# User_Interface.net
KiCad netlist of a schematic drawn in Altium Designer
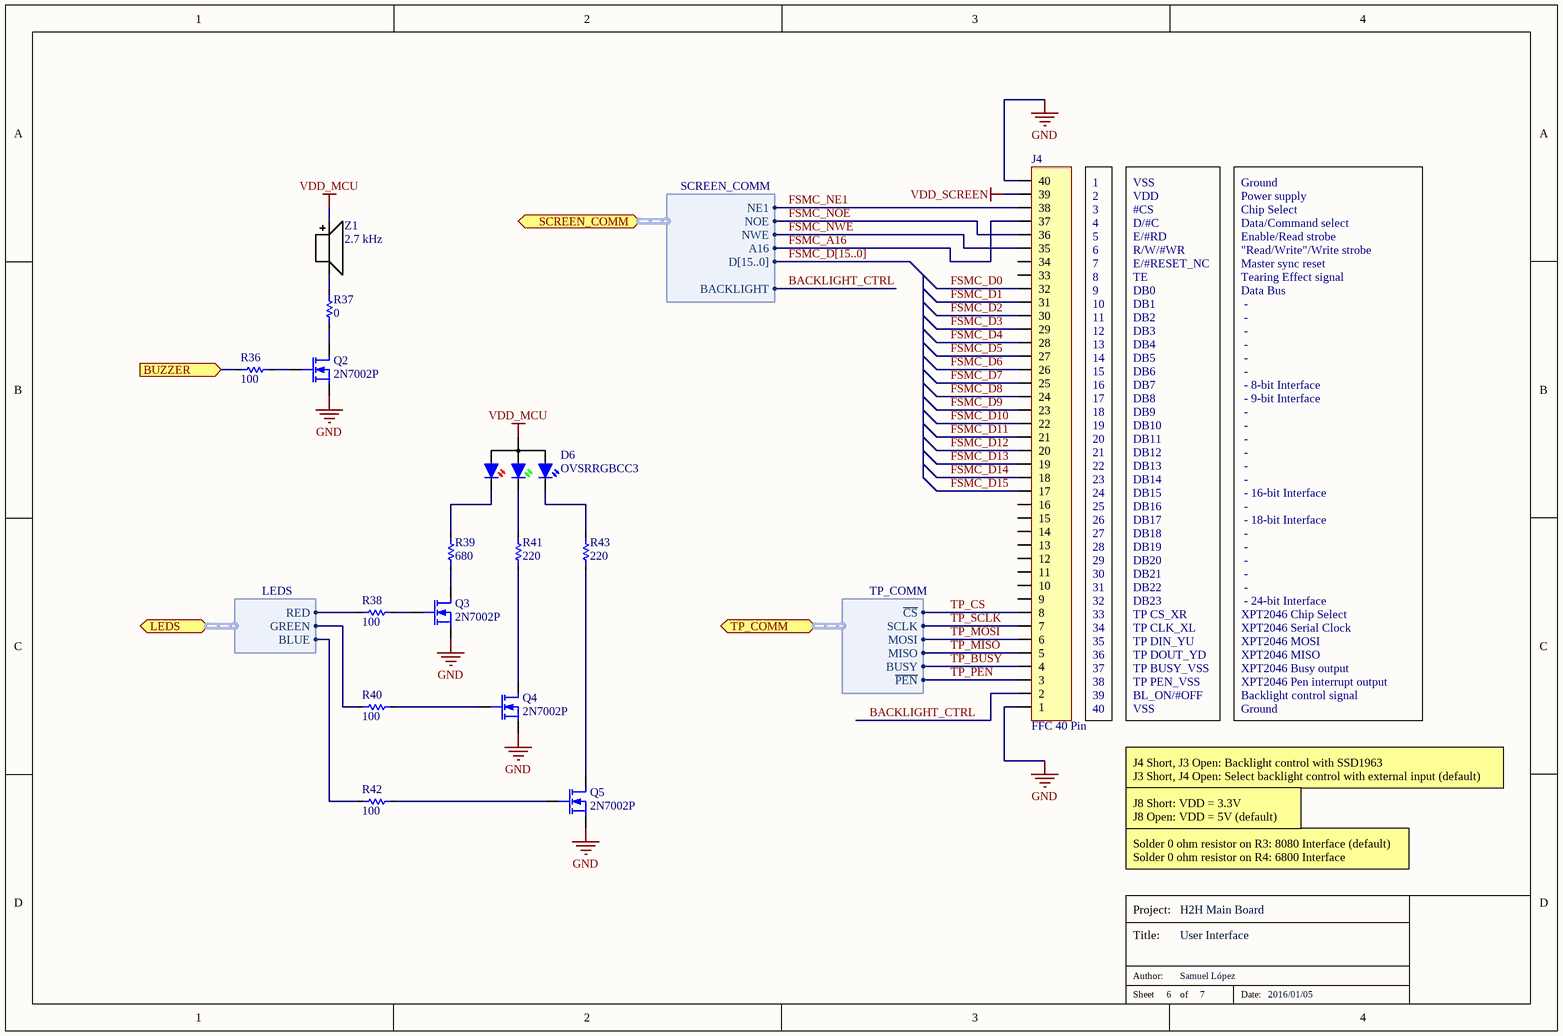
[diagram p0: User Interface.SchDoc]

(export (version "E")
  (design (tool "Eeschema 10.0.6"))
  (components
    (comp (ref "D6")
      (value "OVSRRGBCC3")
      (footprint "OVSRRGBCC3/SIDE")
      (description "LED - RGB, Top/Side-emmiting")
      (libsource (lib "H2H") (part "OVSRRGBCC3"))
    )
    (comp (ref "J4")
      (value "FFC 40 Pin")
      (footprint "ER-CON40HB-2")
      (description "Conn - FFC/FPC, 40 Pin, 1.0mm Pitch, ZIF")
      (libsource (lib "Conn") (part "ER-CON40HB-2"))
    )
    (comp (ref "Q2")
      (value "2N7002P")
      (footprint "2N7002P")
      (description "Transistor - MOSFET, N-Channel, 60V, 300mA")
      (libsource (lib "H2H") (part "2N7002P"))
    )
    (comp (ref "Q3")
      (value "2N7002P")
      (footprint "2N7002P")
      (description "Transistor - MOSFET, N-Channel, 60V, 300mA")
      (libsource (lib "H2H") (part "2N7002P"))
    )
    (comp (ref "Q4")
      (value "2N7002P")
      (footprint "2N7002P")
      (description "Transistor - MOSFET, N-Channel, 60V, 300mA")
      (libsource (lib "H2H") (part "2N7002P"))
    )
    (comp (ref "Q5")
      (value "2N7002P")
      (footprint "2N7002P")
      (description "Transistor - MOSFET, N-Channel, 60V, 300mA")
      (libsource (lib "H2H") (part "2N7002P"))
    )
    (comp (ref "R36")
      (value "100")
      (footprint "R0603")
      (description "Resistor")
      (libsource (lib "Misc") (part "Resistor"))
    )
    (comp (ref "R37")
      (value "0")
      (footprint "R0603")
      (description "Resistor")
      (libsource (lib "Misc") (part "Resistor"))
    )
    (comp (ref "R38")
      (value "100")
      (footprint "R0603")
      (description "Resistor")
      (libsource (lib "Misc") (part "Resistor"))
    )
    (comp (ref "R39")
      (value "680")
      (footprint "R0603")
      (description "Resistor")
      (libsource (lib "Misc") (part "Resistor"))
    )
    (comp (ref "R40")
      (value "100")
      (footprint "R0603")
      (description "Resistor")
      (libsource (lib "Misc") (part "Resistor"))
    )
    (comp (ref "R41")
      (value "220")
      (footprint "R0603")
      (description "Resistor")
      (libsource (lib "Misc") (part "Resistor"))
    )
    (comp (ref "R42")
      (value "100")
      (footprint "R0603")
      (description "Resistor")
      (libsource (lib "Misc") (part "Resistor"))
    )
    (comp (ref "R43")
      (value "220")
      (footprint "R0603")
      (description "Resistor")
      (libsource (lib "Misc") (part "Resistor"))
    )
    (comp (ref "Z1")
      (value "2.7 kHz")
      (footprint "KSSG74B16")
      (description "Transductor - Buzzer 2.7 kHz")
      (libsource (lib "H2H") (part "KSSG74B16"))
    )
  )
  (nets
    (net (code "4") (name "/BACKLIGHT_CTRL") (class "Default")
      (node (ref "J4") (pin "2") (pinfunction "2_2") (pintype "passive"))
    )
    (net (code "5") (name "/BLUE") (class "Default")
      (node (ref "R42") (pin "2") (pinfunction "2_2") (pintype "passive"))
    )
    (net (code "6") (name "/BUZZER") (class "Default")
      (node (ref "R36") (pin "1") (pinfunction "1_1") (pintype "passive"))
    )
    (net (code "7") (name "/FSMC_A16") (class "Default")
      (node (ref "J4") (pin "37") (pinfunction "37_37") (pintype "passive"))
    )
    (net (code "8") (name "/FSMC_D0") (class "Default")
      (node (ref "J4") (pin "32") (pinfunction "32_32") (pintype "passive"))
    )
    (net (code "9") (name "/FSMC_D1") (class "Default")
      (node (ref "J4") (pin "31") (pinfunction "31_31") (pintype "passive"))
    )
    (net (code "10") (name "/FSMC_D2") (class "Default")
      (node (ref "J4") (pin "30") (pinfunction "30_30") (pintype "passive"))
    )
    (net (code "11") (name "/FSMC_D3") (class "Default")
      (node (ref "J4") (pin "29") (pinfunction "29_29") (pintype "passive"))
    )
    (net (code "12") (name "/FSMC_D4") (class "Default")
      (node (ref "J4") (pin "28") (pinfunction "28_28") (pintype "passive"))
    )
    (net (code "13") (name "/FSMC_D5") (class "Default")
      (node (ref "J4") (pin "27") (pinfunction "27_27") (pintype "passive"))
    )
    (net (code "14") (name "/FSMC_D6") (class "Default")
      (node (ref "J4") (pin "26") (pinfunction "26_26") (pintype "passive"))
    )
    (net (code "15") (name "/FSMC_D7") (class "Default")
      (node (ref "J4") (pin "25") (pinfunction "25_25") (pintype "passive"))
    )
    (net (code "16") (name "/FSMC_D8") (class "Default")
      (node (ref "J4") (pin "24") (pinfunction "24_24") (pintype "passive"))
    )
    (net (code "17") (name "/FSMC_D9") (class "Default")
      (node (ref "J4") (pin "23") (pinfunction "23_23") (pintype "passive"))
    )
    (net (code "18") (name "/FSMC_D10") (class "Default")
      (node (ref "J4") (pin "22") (pinfunction "22_22") (pintype "passive"))
    )
    (net (code "19") (name "/FSMC_D11") (class "Default")
      (node (ref "J4") (pin "21") (pinfunction "21_21") (pintype "passive"))
    )
    (net (code "20") (name "/FSMC_D12") (class "Default")
      (node (ref "J4") (pin "20") (pinfunction "20_20") (pintype "passive"))
    )
    (net (code "21") (name "/FSMC_D13") (class "Default")
      (node (ref "J4") (pin "19") (pinfunction "19_19") (pintype "passive"))
    )
    (net (code "22") (name "/FSMC_D14") (class "Default")
      (node (ref "J4") (pin "18") (pinfunction "18_18") (pintype "passive"))
    )
    (net (code "23") (name "/FSMC_D15") (class "Default")
      (node (ref "J4") (pin "17") (pinfunction "17_17") (pintype "passive"))
    )
    (net (code "24") (name "/FSMC_NE1") (class "Default")
      (node (ref "J4") (pin "38") (pinfunction "38_38") (pintype "passive"))
    )
    (net (code "25") (name "/FSMC_NOE") (class "Default")
      (node (ref "J4") (pin "36") (pinfunction "36_36") (pintype "passive"))
    )
    (net (code "26") (name "/FSMC_NWE") (class "Default")
      (node (ref "J4") (pin "35") (pinfunction "35_35") (pintype "passive"))
    )
    (net (code "27") (name "/GREEN") (class "Default")
      (node (ref "R40") (pin "1") (pinfunction "1_1") (pintype "passive"))
    )
    (net (code "28") (name "/RED") (class "Default")
      (node (ref "R38") (pin "1") (pinfunction "1_1") (pintype "passive"))
    )
    (net (code "30") (name "/TP_BUSY") (class "Default")
      (node (ref "J4") (pin "4") (pinfunction "4_4") (pintype "passive"))
    )
    (net (code "31") (name "/TP_CS") (class "Default")
      (node (ref "J4") (pin "8") (pinfunction "8_8") (pintype "passive"))
    )
    (net (code "32") (name "/TP_MISO") (class "Default")
      (node (ref "J4") (pin "5") (pinfunction "5_5") (pintype "passive"))
    )
    (net (code "33") (name "/TP_MOSI") (class "Default")
      (node (ref "J4") (pin "6") (pinfunction "6_6") (pintype "passive"))
    )
    (net (code "34") (name "/TP_PEN") (class "Default")
      (node (ref "J4") (pin "3") (pinfunction "3_3") (pintype "passive"))
    )
    (net (code "35") (name "/TP_SCLK") (class "Default")
      (node (ref "J4") (pin "7") (pinfunction "7_7") (pintype "passive"))
    )
    (net (code "39") (name "GND") (class "Default")
      (node (ref "J4") (pin "1") (pinfunction "1_1") (pintype "passive"))
      (node (ref "J4") (pin "40") (pinfunction "40_40") (pintype "passive"))
      (node (ref "Q2") (pin "2") (pinfunction "S_2") (pintype "passive"))
      (node (ref "Q3") (pin "2") (pinfunction "S_2") (pintype "passive"))
      (node (ref "Q4") (pin "2") (pinfunction "S_2") (pintype "passive"))
      (node (ref "Q5") (pin "2") (pinfunction "S_2") (pintype "passive"))
    )
    (net (code "40") (name "Net-(D6-K_B)") (class "Default")
      (node (ref "D6") (pin "3") (pinfunction "K_B_3") (pintype "passive"))
      (node (ref "R43") (pin "2") (pinfunction "2_2") (pintype "passive"))
    )
    (net (code "41") (name "Net-(D6-K_G)") (class "Default")
      (node (ref "D6") (pin "2") (pinfunction "K_G_2") (pintype "passive"))
      (node (ref "R41") (pin "1") (pinfunction "1_1") (pintype "passive"))
    )
    (net (code "42") (name "Net-(D6-K_R)") (class "Default")
      (node (ref "D6") (pin "1") (pinfunction "K_R_1") (pintype "passive"))
      (node (ref "R39") (pin "2") (pinfunction "2_2") (pintype "passive"))
    )
    (net (code "43") (name "Net-(Q2-D)") (class "Default")
      (node (ref "Q2") (pin "3") (pinfunction "D_3") (pintype "passive"))
      (node (ref "R37") (pin "2") (pinfunction "2_2") (pintype "passive"))
    )
    (net (code "44") (name "Net-(Q2-G)") (class "Default")
      (node (ref "Q2") (pin "1") (pinfunction "G_1") (pintype "passive"))
      (node (ref "R36") (pin "2") (pinfunction "2_2") (pintype "passive"))
    )
    (net (code "45") (name "Net-(Q3-D)") (class "Default")
      (node (ref "Q3") (pin "3") (pinfunction "D_3") (pintype "passive"))
      (node (ref "R39") (pin "1") (pinfunction "1_1") (pintype "passive"))
    )
    (net (code "46") (name "Net-(Q3-G)") (class "Default")
      (node (ref "Q3") (pin "1") (pinfunction "G_1") (pintype "passive"))
      (node (ref "R38") (pin "2") (pinfunction "2_2") (pintype "passive"))
    )
    (net (code "47") (name "Net-(Q4-D)") (class "Default")
      (node (ref "Q4") (pin "3") (pinfunction "D_3") (pintype "passive"))
      (node (ref "R41") (pin "2") (pinfunction "2_2") (pintype "passive"))
    )
    (net (code "48") (name "Net-(Q4-G)") (class "Default")
      (node (ref "Q4") (pin "1") (pinfunction "G_1") (pintype "passive"))
      (node (ref "R40") (pin "2") (pinfunction "2_2") (pintype "passive"))
    )
    (net (code "49") (name "Net-(Q5-D)") (class "Default")
      (node (ref "Q5") (pin "3") (pinfunction "D_3") (pintype "passive"))
      (node (ref "R43") (pin "1") (pinfunction "1_1") (pintype "passive"))
    )
    (net (code "50") (name "Net-(Q5-G)") (class "Default")
      (node (ref "Q5") (pin "1") (pinfunction "G_1") (pintype "passive"))
      (node (ref "R42") (pin "1") (pinfunction "1_1") (pintype "passive"))
    )
    (net (code "51") (name "Net-(Z1--)") (class "Default")
      (node (ref "R37") (pin "1") (pinfunction "1_1") (pintype "passive"))
      (node (ref "Z1") (pin "2") (pinfunction "-_2") (pintype "passive"))
    )
    (net (code "52") (name "VDD_MCU") (class "Default")
      (node (ref "D6") (pin "4") (pinfunction "A_4") (pintype "passive"))
      (node (ref "Z1") (pin "1") (pinfunction "+_1") (pintype "passive"))
    )
    (net (code "53") (name "VDD_SCREEN") (class "Default")
      (node (ref "J4") (pin "39") (pinfunction "39_39") (pintype "passive"))
    )
    (net (code "54") (name "unconnected-(J4-Pad9)") (class "Default")
      (node (ref "J4") (pin "9") (pinfunction "9_9") (pintype "passive"))
    )
    (net (code "55") (name "unconnected-(J4-Pad10)") (class "Default")
      (node (ref "J4") (pin "10") (pinfunction "10_10") (pintype "passive"))
    )
    (net (code "56") (name "unconnected-(J4-Pad11)") (class "Default")
      (node (ref "J4") (pin "11") (pinfunction "11_11") (pintype "passive"))
    )
    (net (code "57") (name "unconnected-(J4-Pad12)") (class "Default")
      (node (ref "J4") (pin "12") (pinfunction "12_12") (pintype "passive"))
    )
    (net (code "58") (name "unconnected-(J4-Pad13)") (class "Default")
      (node (ref "J4") (pin "13") (pinfunction "13_13") (pintype "passive"))
    )
    (net (code "59") (name "unconnected-(J4-Pad14)") (class "Default")
      (node (ref "J4") (pin "14") (pinfunction "14_14") (pintype "passive"))
    )
    (net (code "60") (name "unconnected-(J4-Pad15)") (class "Default")
      (node (ref "J4") (pin "15") (pinfunction "15_15") (pintype "passive"))
    )
    (net (code "61") (name "unconnected-(J4-Pad16)") (class "Default")
      (node (ref "J4") (pin "16") (pinfunction "16_16") (pintype "passive"))
    )
    (net (code "62") (name "unconnected-(J4-Pad33)") (class "Default")
      (node (ref "J4") (pin "33") (pinfunction "33_33") (pintype "passive"))
    )
    (net (code "63") (name "unconnected-(J4-Pad34)") (class "Default")
      (node (ref "J4") (pin "34") (pinfunction "34_34") (pintype "passive"))
    )
  )
)
